# Laser_Terminal_new.net
KiCad netlist of a schematic drawn in EAGLE
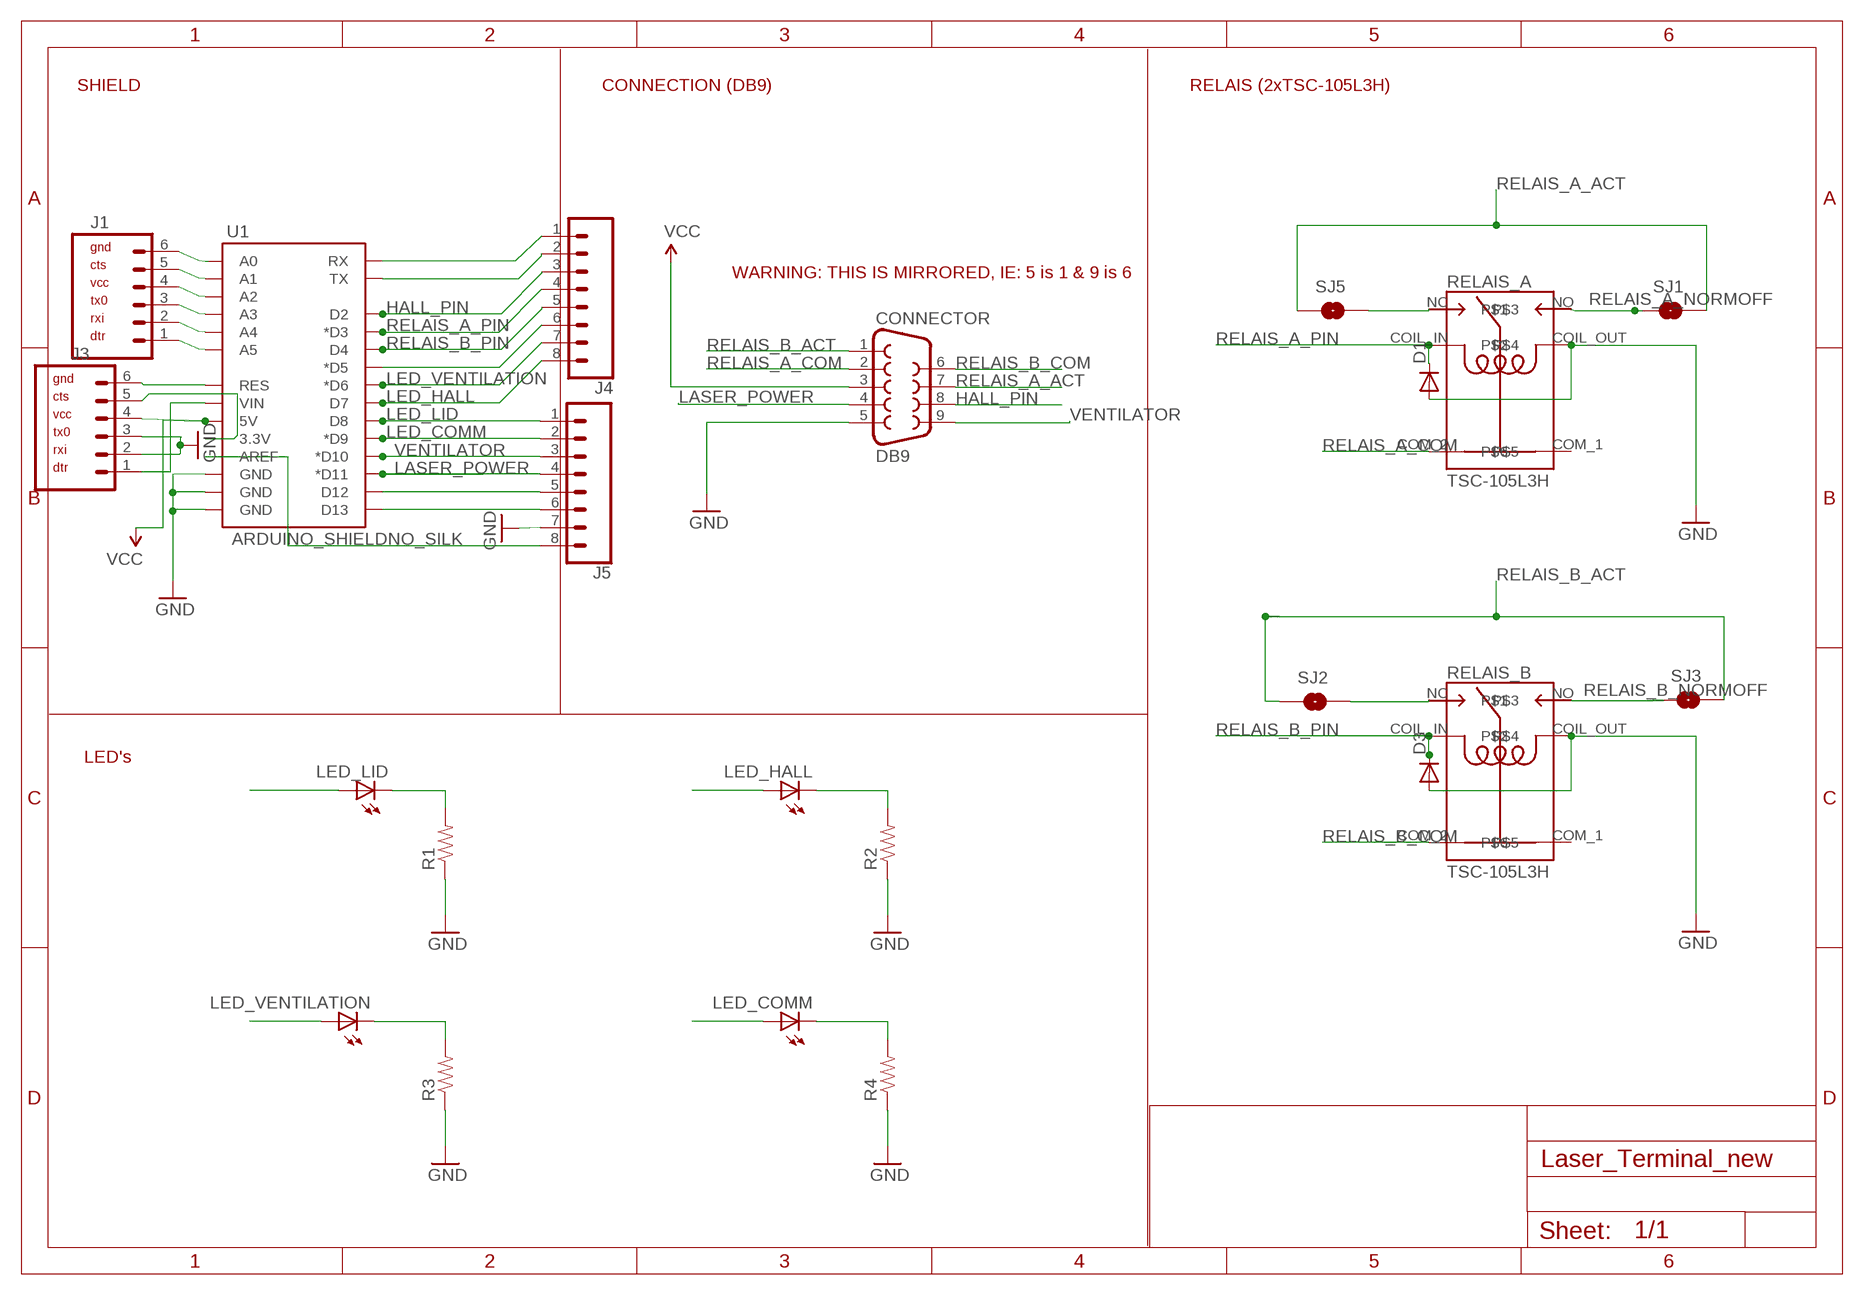
[diagram p0: schematic, sheet 1]

(export (version "E")
  (design (tool "Eeschema 10.0.6"))
  (components
    (comp (ref "CONNECTOR")
      (value "DB9")
      (footprint "eagle-import:DB9_MALE")
      (libsource (lib "eagle-import") (part "DB9MALE"))
    )
    (comp (ref "D1")
      (value "DIODEPTH")
      (footprint "eagle-import:DIODE-1N4001")
      (libsource (lib "eagle-import") (part "DIODEPTH"))
    )
    (comp (ref "D3")
      (value "DIODEPTH")
      (footprint "eagle-import:DIODE-1N4001")
      (libsource (lib "eagle-import") (part "DIODEPTH"))
    )
    (comp (ref "J1")
      (value "M06NO_SILK_YES_STOP")
      (footprint "eagle-import:1X06_NO_SILK_YES_STOP")
      (libsource (lib "eagle-import") (part "M06NO_SILK_YES_STOP"))
    )
    (comp (ref "J3")
      (value "M06NO_SILK_YES_STOP")
      (footprint "eagle-import:1X06_NO_SILK_YES_STOP")
      (libsource (lib "eagle-import") (part "M06NO_SILK_YES_STOP"))
    )
    (comp (ref "J4")
      (value "CONN_08\"")
      (footprint "eagle-import:1X08")
      (libsource (lib "eagle-import") (part "CONN_08{dblquote}"))
    )
    (comp (ref "J5")
      (value "CONN_08\"")
      (footprint "eagle-import:1X08")
      (libsource (lib "eagle-import") (part "CONN_08{dblquote}"))
    )
    (comp (ref "LED_COMM")
      (value "LED5MM")
      (footprint "eagle-import:LED5MM")
      (libsource (lib "eagle-import") (part "LED5MM"))
    )
    (comp (ref "LED_HALL")
      (value "LED5MM")
      (footprint "eagle-import:LED5MM")
      (libsource (lib "eagle-import") (part "LED5MM"))
    )
    (comp (ref "LED_LID")
      (value "LED5MM")
      (footprint "eagle-import:LED5MM")
      (libsource (lib "eagle-import") (part "LED5MM"))
    )
    (comp (ref "LED_VENTILATION")
      (value "LED5MM")
      (footprint "eagle-import:LED5MM")
      (libsource (lib "eagle-import") (part "LED5MM"))
    )
    (comp (ref "R1")
      (value "RESISTORAXIAL-0.3")
      (footprint "eagle-import:AXIAL-0.3")
      (libsource (lib "eagle-import") (part "RESISTORAXIAL-0.3"))
    )
    (comp (ref "R2")
      (value "RESISTORAXIAL-0.3")
      (footprint "eagle-import:AXIAL-0.3")
      (libsource (lib "eagle-import") (part "RESISTORAXIAL-0.3"))
    )
    (comp (ref "R3")
      (value "RESISTORAXIAL-0.3")
      (footprint "eagle-import:AXIAL-0.3")
      (libsource (lib "eagle-import") (part "RESISTORAXIAL-0.3"))
    )
    (comp (ref "R4")
      (value "RESISTORAXIAL-0.3")
      (footprint "eagle-import:AXIAL-0.3")
      (libsource (lib "eagle-import") (part "RESISTORAXIAL-0.3"))
    )
    (comp (ref "RELAIS_A")
      (value "TSC-105L3H")
      (footprint "eagle-import:TSC_112L3H")
      (libsource (lib "eagle-import") (part "TSC-112L3H"))
    )
    (comp (ref "RELAIS_B")
      (value "TSC-105L3H")
      (footprint "eagle-import:TSC_112L3H")
      (libsource (lib "eagle-import") (part "TSC-112L3H"))
    )
    (comp (ref "SJ1")
      (value "SOLDERJUMPERNO")
      (footprint "eagle-import:SJ_2S-NO")
      (libsource (lib "eagle-import") (part "SOLDERJUMPERNO"))
    )
    (comp (ref "SJ2")
      (value "SOLDERJUMPERNO")
      (footprint "eagle-import:SJ_2S-NO")
      (libsource (lib "eagle-import") (part "SOLDERJUMPERNO"))
    )
    (comp (ref "SJ3")
      (value "JUMPER-SMT_2_NO_SILK")
      (footprint "eagle-import:SMT-JUMPER_2_NO_SILK")
      (libsource (lib "eagle-import") (part "JUMPER-SMT_2_NO_SILK"))
    )
    (comp (ref "SJ5")
      (value "SOLDERJUMPERNO")
      (footprint "eagle-import:SJ_2S-NO")
      (libsource (lib "eagle-import") (part "SOLDERJUMPERNO"))
    )
    (comp (ref "U1")
      (value "ARDUINO_SHIELDNO_SILK")
      (footprint "eagle-import:DUEMILANOVE_VIAS")
      (libsource (lib "eagle-import") (part "ARDUINO_SHIELDNO_SILK"))
    )
  )
  (nets
    (net (code "1") (name "/HALL_PIN") (class "Default")
      (node (ref "CONNECTOR") (pin "8") (pinfunction "8_8") (pintype "passive"))
      (node (ref "J4") (pin "3") (pinfunction "3_3") (pintype "passive"))
      (node (ref "U1") (pin "D2") (pinfunction "D2_D2") (pintype "bidirectional"))
    )
    (net (code "2") (name "/LASER_POWER") (class "Default")
      (node (ref "CONNECTOR") (pin "4") (pinfunction "4_4") (pintype "passive"))
      (node (ref "J5") (pin "4") (pinfunction "4_4") (pintype "passive"))
      (node (ref "U1") (pin "D11") (pinfunction "*D11_D11") (pintype "bidirectional"))
    )
    (net (code "3") (name "/LED_COMM") (class "Default")
      (node (ref "J5") (pin "2") (pinfunction "2_2") (pintype "passive"))
      (node (ref "LED_COMM") (pin "A") (pinfunction "A_A") (pintype "passive"))
      (node (ref "U1") (pin "D9") (pinfunction "*D9_D9") (pintype "bidirectional"))
    )
    (net (code "4") (name "/LED_HALL") (class "Default")
      (node (ref "J4") (pin "8") (pinfunction "8_8") (pintype "passive"))
      (node (ref "LED_HALL") (pin "A") (pinfunction "A_A") (pintype "passive"))
      (node (ref "U1") (pin "D7") (pinfunction "D7_D7") (pintype "bidirectional"))
    )
    (net (code "5") (name "/LED_LID") (class "Default")
      (node (ref "J5") (pin "1") (pinfunction "1_1") (pintype "passive"))
      (node (ref "LED_LID") (pin "A") (pinfunction "A_A") (pintype "passive"))
      (node (ref "U1") (pin "D8") (pinfunction "D8_D8") (pintype "bidirectional"))
    )
    (net (code "6") (name "/LED_VENTILATION") (class "Default")
      (node (ref "J4") (pin "7") (pinfunction "7_7") (pintype "passive"))
      (node (ref "LED_VENTILATION") (pin "A") (pinfunction "A_A") (pintype "passive"))
      (node (ref "U1") (pin "D6") (pinfunction "*D6_D6") (pintype "bidirectional"))
    )
    (net (code "7") (name "/RELAIS_A_ACT") (class "Default")
      (node (ref "CONNECTOR") (pin "7") (pinfunction "7_7") (pintype "passive"))
      (node (ref "SJ1") (pin "2") (pinfunction "2_2") (pintype "passive"))
      (node (ref "SJ5") (pin "1") (pinfunction "1_1") (pintype "passive"))
    )
    (net (code "8") (name "/RELAIS_A_COM") (class "Default")
      (node (ref "CONNECTOR") (pin "2") (pinfunction "2_2") (pintype "passive"))
      (node (ref "RELAIS_A") (pin "COM_2") (pinfunction "P$6_COM_2") (pintype "bidirectional"))
    )
    (net (code "9") (name "/RELAIS_A_NORMOFF") (class "Default")
      (node (ref "RELAIS_A") (pin "NO") (pinfunction "P$3_NO") (pintype "bidirectional"))
      (node (ref "SJ1") (pin "1") (pinfunction "1_1") (pintype "passive"))
    )
    (net (code "10") (name "/RELAIS_A_PIN") (class "Default")
      (node (ref "D1") (pin "C") (pinfunction "C_C") (pintype "passive"))
      (node (ref "J4") (pin "4") (pinfunction "4_4") (pintype "passive"))
      (node (ref "RELAIS_A") (pin "COIL_IN") (pinfunction "P$2_COIL_IN") (pintype "bidirectional"))
      (node (ref "U1") (pin "D3") (pinfunction "*D3_D3") (pintype "bidirectional"))
    )
    (net (code "11") (name "/RELAIS_B_ACT") (class "Default")
      (node (ref "CONNECTOR") (pin "1") (pinfunction "1_1") (pintype "passive"))
      (node (ref "SJ2") (pin "1") (pinfunction "1_1") (pintype "passive"))
      (node (ref "SJ3") (pin "2") (pinfunction "2_2") (pintype "passive"))
    )
    (net (code "12") (name "/RELAIS_B_COM") (class "Default")
      (node (ref "CONNECTOR") (pin "6") (pinfunction "6_6") (pintype "passive"))
      (node (ref "RELAIS_B") (pin "COM_2") (pinfunction "P$6_COM_2") (pintype "bidirectional"))
    )
    (net (code "13") (name "/RELAIS_B_NORMOFF") (class "Default")
      (node (ref "RELAIS_B") (pin "NO") (pinfunction "P$3_NO") (pintype "bidirectional"))
      (node (ref "SJ3") (pin "1") (pinfunction "1_1") (pintype "passive"))
    )
    (net (code "14") (name "/RELAIS_B_PIN") (class "Default")
      (node (ref "D3") (pin "C") (pinfunction "C_C") (pintype "passive"))
      (node (ref "J4") (pin "5") (pinfunction "5_5") (pintype "passive"))
      (node (ref "RELAIS_B") (pin "COIL_IN") (pinfunction "P$2_COIL_IN") (pintype "bidirectional"))
      (node (ref "U1") (pin "D4") (pinfunction "D4_D4") (pintype "bidirectional"))
    )
    (net (code "15") (name "/VENTILATOR") (class "Default")
      (node (ref "CONNECTOR") (pin "9") (pinfunction "9_9") (pintype "passive"))
      (node (ref "J5") (pin "3") (pinfunction "3_3") (pintype "passive"))
      (node (ref "U1") (pin "D10") (pinfunction "*D10_D10") (pintype "bidirectional"))
    )
    (net (code "16") (name "GND") (class "Default")
      (node (ref "CONNECTOR") (pin "5") (pinfunction "5_5") (pintype "passive"))
      (node (ref "D1") (pin "A") (pinfunction "A_A") (pintype "passive"))
      (node (ref "D3") (pin "A") (pinfunction "A_A") (pintype "passive"))
      (node (ref "J3") (pin "2") (pinfunction "2_2") (pintype "passive"))
      (node (ref "J3") (pin "3") (pinfunction "3_3") (pintype "passive"))
      (node (ref "J5") (pin "7") (pinfunction "7_7") (pintype "passive"))
      (node (ref "R1") (pin "P$1") (pinfunction "1_P$1") (pintype "passive"))
      (node (ref "R2") (pin "P$1") (pinfunction "1_P$1") (pintype "passive"))
      (node (ref "R3") (pin "P$1") (pinfunction "1_P$1") (pintype "passive"))
      (node (ref "R4") (pin "P$1") (pinfunction "1_P$1") (pintype "passive"))
      (node (ref "RELAIS_A") (pin "COIL_OUT") (pinfunction "P$4_COIL_OUT") (pintype "bidirectional"))
      (node (ref "RELAIS_B") (pin "COIL_OUT") (pinfunction "P$4_COIL_OUT") (pintype "bidirectional"))
      (node (ref "U1") (pin "GND@0") (pinfunction "GND_GND@0") (pintype "bidirectional"))
      (node (ref "U1") (pin "GND@1") (pinfunction "GND_GND@1") (pintype "bidirectional"))
      (node (ref "U1") (pin "GND@2") (pinfunction "GND_GND@2") (pintype "bidirectional"))
    )
    (net (code "17") (name "Net-(J1-Pad1)") (class "Default")
      (node (ref "J1") (pin "1") (pinfunction "1_1") (pintype "passive"))
      (node (ref "U1") (pin "A5") (pinfunction "A5_A5") (pintype "bidirectional"))
    )
    (net (code "18") (name "Net-(J1-Pad2)") (class "Default")
      (node (ref "J1") (pin "2") (pinfunction "2_2") (pintype "passive"))
      (node (ref "U1") (pin "A4") (pinfunction "A4_A4") (pintype "bidirectional"))
    )
    (net (code "19") (name "Net-(J1-Pad3)") (class "Default")
      (node (ref "J1") (pin "3") (pinfunction "3_3") (pintype "passive"))
      (node (ref "U1") (pin "A3") (pinfunction "A3_A3") (pintype "bidirectional"))
    )
    (net (code "20") (name "Net-(J1-Pad4)") (class "Default")
      (node (ref "J1") (pin "4") (pinfunction "4_4") (pintype "passive"))
      (node (ref "U1") (pin "A2") (pinfunction "A2_A2") (pintype "bidirectional"))
    )
    (net (code "21") (name "Net-(J1-Pad5)") (class "Default")
      (node (ref "J1") (pin "5") (pinfunction "5_5") (pintype "passive"))
      (node (ref "U1") (pin "A1") (pinfunction "A1_A1") (pintype "bidirectional"))
    )
    (net (code "22") (name "Net-(J1-Pad6)") (class "Default")
      (node (ref "J1") (pin "6") (pinfunction "6_6") (pintype "passive"))
      (node (ref "U1") (pin "A0") (pinfunction "A0_A0") (pintype "bidirectional"))
    )
    (net (code "23") (name "Net-(J3-Pad1)") (class "Default")
      (node (ref "J3") (pin "1") (pinfunction "1_1") (pintype "passive"))
      (node (ref "U1") (pin "VIN") (pinfunction "VIN_VIN") (pintype "bidirectional"))
    )
    (net (code "24") (name "Net-(J3-Pad5)") (class "Default")
      (node (ref "J3") (pin "5") (pinfunction "5_5") (pintype "passive"))
      (node (ref "U1") (pin "3.3V") (pinfunction "3.3V_3.3V") (pintype "bidirectional"))
    )
    (net (code "25") (name "Net-(J3-Pad6)") (class "Default")
      (node (ref "J3") (pin "6") (pinfunction "6_6") (pintype "passive"))
      (node (ref "U1") (pin "RES") (pinfunction "RES_RES") (pintype "bidirectional"))
    )
    (net (code "26") (name "Net-(J4-Pad1)") (class "Default")
      (node (ref "J4") (pin "1") (pinfunction "1_1") (pintype "passive"))
      (node (ref "U1") (pin "RX") (pinfunction "RX_RX") (pintype "bidirectional"))
    )
    (net (code "27") (name "Net-(J4-Pad2)") (class "Default")
      (node (ref "J4") (pin "2") (pinfunction "2_2") (pintype "passive"))
      (node (ref "U1") (pin "TX") (pinfunction "TX_TX") (pintype "bidirectional"))
    )
    (net (code "28") (name "Net-(J5-Pad5)") (class "Default")
      (node (ref "J5") (pin "5") (pinfunction "5_5") (pintype "passive"))
      (node (ref "U1") (pin "D12") (pinfunction "D12_D12") (pintype "bidirectional"))
    )
    (net (code "29") (name "Net-(J5-Pad6)") (class "Default")
      (node (ref "J5") (pin "6") (pinfunction "6_6") (pintype "passive"))
      (node (ref "U1") (pin "D13") (pinfunction "D13_D13") (pintype "bidirectional"))
    )
    (net (code "30") (name "Net-(J5-Pad8)") (class "Default")
      (node (ref "J5") (pin "8") (pinfunction "8_8") (pintype "passive"))
      (node (ref "U1") (pin "AREF") (pinfunction "AREF_AREF") (pintype "bidirectional"))
    )
    (net (code "31") (name "Net-(LED_COMM-C)") (class "Default")
      (node (ref "LED_COMM") (pin "K") (pinfunction "C_K") (pintype "passive"))
      (node (ref "R4") (pin "P$2") (pinfunction "2_P$2") (pintype "passive"))
    )
    (net (code "32") (name "Net-(LED_HALL-C)") (class "Default")
      (node (ref "LED_HALL") (pin "K") (pinfunction "C_K") (pintype "passive"))
      (node (ref "R2") (pin "P$2") (pinfunction "2_P$2") (pintype "passive"))
    )
    (net (code "33") (name "Net-(LED_LID-C)") (class "Default")
      (node (ref "LED_LID") (pin "K") (pinfunction "C_K") (pintype "passive"))
      (node (ref "R1") (pin "P$2") (pinfunction "2_P$2") (pintype "passive"))
    )
    (net (code "34") (name "Net-(LED_VENTILATION-C)") (class "Default")
      (node (ref "LED_VENTILATION") (pin "K") (pinfunction "C_K") (pintype "passive"))
      (node (ref "R3") (pin "P$2") (pinfunction "2_P$2") (pintype "passive"))
    )
    (net (code "35") (name "Net-(RELAIS_A-P$1)") (class "Default")
      (node (ref "RELAIS_A") (pin "NC") (pinfunction "P$1_NC") (pintype "bidirectional"))
      (node (ref "SJ5") (pin "2") (pinfunction "2_2") (pintype "passive"))
    )
    (net (code "36") (name "Net-(RELAIS_B-P$1)") (class "Default")
      (node (ref "RELAIS_B") (pin "NC") (pinfunction "P$1_NC") (pintype "bidirectional"))
      (node (ref "SJ2") (pin "2") (pinfunction "2_2") (pintype "passive"))
    )
    (net (code "37") (name "Net-(U1-*D5)") (class "Default")
      (node (ref "J4") (pin "6") (pinfunction "6_6") (pintype "passive"))
      (node (ref "U1") (pin "D5") (pinfunction "*D5_D5") (pintype "bidirectional"))
    )
    (net (code "38") (name "VCC") (class "Default")
      (node (ref "CONNECTOR") (pin "3") (pinfunction "3_3") (pintype "passive"))
      (node (ref "J3") (pin "4") (pinfunction "4_4") (pintype "passive"))
      (node (ref "U1") (pin "5V") (pinfunction "5V_5V") (pintype "bidirectional"))
    )
    (net (code "39") (name "unconnected-(RELAIS_A-P$5-PadCOM_1)") (class "Default")
      (node (ref "RELAIS_A") (pin "COM_1") (pinfunction "P$5_COM_1") (pintype "bidirectional"))
    )
    (net (code "40") (name "unconnected-(RELAIS_B-P$5-PadCOM_1)") (class "Default")
      (node (ref "RELAIS_B") (pin "COM_1") (pinfunction "P$5_COM_1") (pintype "bidirectional"))
    )
  )
)
